# C64Cart.net
KiCad netlist of a schematic drawn in EAGLE
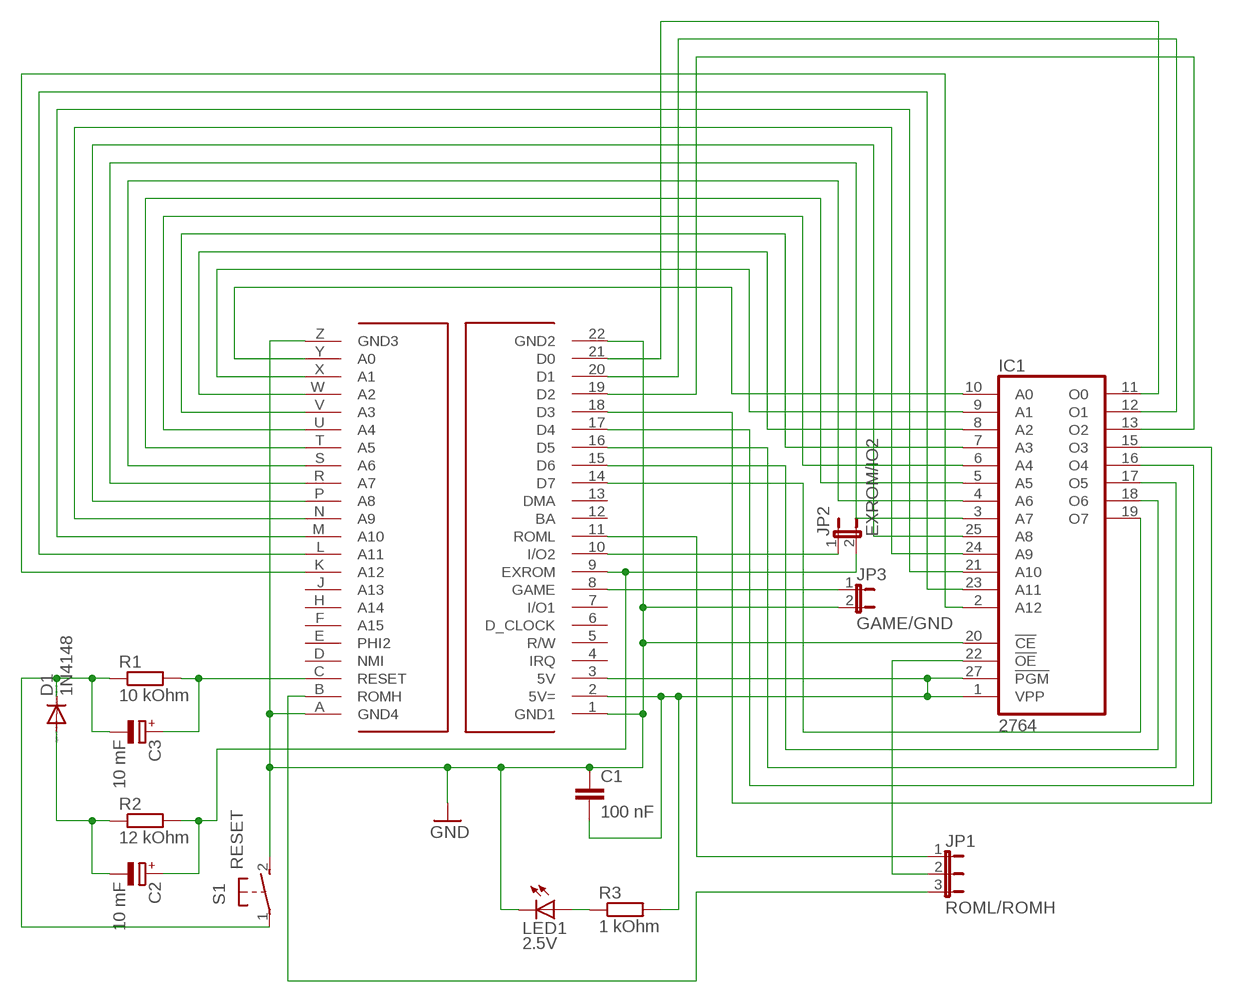
[diagram p0: schematic, sheet 1]

(export (version "E")
  (design (tool "Eeschema 10.0.6"))
  (components
    (comp (ref "C1")
      (value "100 nF")
      (footprint "eagle-import:C050-025X075")
      (libsource (lib "eagle-import") (part "C-EU050-025X075"))
    )
    (comp (ref "C2")
      (value "10 mF")
      (footprint "eagle-import:E2-5")
      (libsource (lib "eagle-import") (part "CPOL-EUE2-5"))
    )
    (comp (ref "C3")
      (value "10 mF")
      (footprint "eagle-import:E2-5")
      (libsource (lib "eagle-import") (part "CPOL-EUE2-5"))
    )
    (comp (ref "D1")
      (value "1N4148")
      (footprint "eagle-import:DO35-7")
      (libsource (lib "eagle-import") (part "1N4148DO35-7"))
    )
    (comp (ref "IC1")
      (value "2764")
      (footprint "eagle-import:DIL28")
      (libsource (lib "eagle-import") (part "2764"))
    )
    (comp (ref "JP1")
      (value "ROML/ROMH")
      (footprint "eagle-import:JP2")
      (libsource (lib "eagle-import") (part "JP2E"))
    )
    (comp (ref "JP2")
      (value "EXROM/IO2")
      (footprint "eagle-import:JP1")
      (libsource (lib "eagle-import") (part "JP1E"))
    )
    (comp (ref "JP3")
      (value "GAME/GND")
      (footprint "eagle-import:JP1")
      (libsource (lib "eagle-import") (part "JP1E"))
    )
    (comp (ref "LED1")
      (value "2.5V")
      (footprint "eagle-import:LED3MM")
      (libsource (lib "eagle-import") (part "LED3MM"))
    )
    (comp (ref "R1")
      (value "10 kOhm")
      (footprint "eagle-import:0204_7")
      (libsource (lib "eagle-import") (part "R-EU_0204/7"))
    )
    (comp (ref "R2")
      (value "12 kOhm")
      (footprint "eagle-import:0204_7")
      (libsource (lib "eagle-import") (part "R-EU_0204/7"))
    )
    (comp (ref "R3")
      (value "1 kOhm")
      (footprint "eagle-import:0204_7")
      (libsource (lib "eagle-import") (part "R-EU_0204/7"))
    )
    (comp (ref "S1")
      (value "RESET")
      (footprint "eagle-import:B3F-31XX")
      (fields (field (name "MPN") "B3F-3100"))
      (libsource (lib "eagle-import") (part "31-XX"))
    )
    (comp (ref "U$1")
      (value "C64_CN")
      (footprint "eagle-import:CARTRIDGE")
      (libsource (lib "eagle-import") (part "CARTRIDGE"))
    )
  )
  (nets
    (net (code "1") (name "GND") (class "Default")
      (node (ref "C1") (pin "1") (pinfunction "1_1") (pintype "passive"))
      (node (ref "IC1") (pin "20") (pinfunction "~{CE}_20") (pintype "input"))
      (node (ref "JP3") (pin "2") (pinfunction "2_2") (pintype "passive"))
      (node (ref "LED1") (pin "K") (pinfunction "C_K") (pintype "passive"))
      (node (ref "S1") (pin "2") (pinfunction "S_2") (pintype "passive"))
      (node (ref "U$1") (pin "1") (pinfunction "GND1_1") (pintype "bidirectional"))
      (node (ref "U$1") (pin "22") (pinfunction "GND2_22") (pintype "bidirectional"))
      (node (ref "U$1") (pin "A") (pinfunction "GND4_A") (pintype "bidirectional"))
      (node (ref "U$1") (pin "Z") (pinfunction "GND3_Z") (pintype "bidirectional"))
    )
    (net (code "2") (name "Net-(C2-Pad-)") (class "Default")
      (node (ref "C2") (pin "-") (pinfunction "-_-") (pintype "passive"))
      (node (ref "D1") (pin "A") (pinfunction "A_A") (pintype "passive"))
      (node (ref "R2") (pin "1") (pinfunction "1_1") (pintype "passive"))
    )
    (net (code "3") (name "Net-(IC1A-A0)") (class "Default")
      (node (ref "IC1") (pin "10") (pinfunction "A0_10") (pintype "input"))
      (node (ref "U$1") (pin "Y") (pinfunction "A0_Y") (pintype "bidirectional"))
    )
    (net (code "4") (name "Net-(IC1A-A1)") (class "Default")
      (node (ref "IC1") (pin "9") (pinfunction "A1_9") (pintype "input"))
      (node (ref "U$1") (pin "X") (pinfunction "A1_X") (pintype "bidirectional"))
    )
    (net (code "5") (name "Net-(IC1A-A2)") (class "Default")
      (node (ref "IC1") (pin "8") (pinfunction "A2_8") (pintype "input"))
      (node (ref "U$1") (pin "W") (pinfunction "A2_W") (pintype "bidirectional"))
    )
    (net (code "6") (name "Net-(IC1A-A3)") (class "Default")
      (node (ref "IC1") (pin "7") (pinfunction "A3_7") (pintype "input"))
      (node (ref "U$1") (pin "V") (pinfunction "A3_V") (pintype "bidirectional"))
    )
    (net (code "7") (name "Net-(IC1A-A4)") (class "Default")
      (node (ref "IC1") (pin "6") (pinfunction "A4_6") (pintype "input"))
      (node (ref "U$1") (pin "U") (pinfunction "A4_U") (pintype "bidirectional"))
    )
    (net (code "8") (name "Net-(IC1A-A5)") (class "Default")
      (node (ref "IC1") (pin "5") (pinfunction "A5_5") (pintype "input"))
      (node (ref "U$1") (pin "T") (pinfunction "A5_T") (pintype "bidirectional"))
    )
    (net (code "9") (name "Net-(IC1A-A6)") (class "Default")
      (node (ref "IC1") (pin "4") (pinfunction "A6_4") (pintype "input"))
      (node (ref "U$1") (pin "S") (pinfunction "A6_S") (pintype "bidirectional"))
    )
    (net (code "10") (name "Net-(IC1A-A7)") (class "Default")
      (node (ref "IC1") (pin "3") (pinfunction "A7_3") (pintype "input"))
      (node (ref "U$1") (pin "R") (pinfunction "A7_R") (pintype "bidirectional"))
    )
    (net (code "11") (name "Net-(IC1A-A8)") (class "Default")
      (node (ref "IC1") (pin "25") (pinfunction "A8_25") (pintype "input"))
      (node (ref "U$1") (pin "P") (pinfunction "A8_P") (pintype "bidirectional"))
    )
    (net (code "12") (name "Net-(IC1A-A9)") (class "Default")
      (node (ref "IC1") (pin "24") (pinfunction "A9_24") (pintype "input"))
      (node (ref "U$1") (pin "N") (pinfunction "A9_N") (pintype "bidirectional"))
    )
    (net (code "13") (name "Net-(IC1A-A10)") (class "Default")
      (node (ref "IC1") (pin "21") (pinfunction "A10_21") (pintype "input"))
      (node (ref "U$1") (pin "M") (pinfunction "A10_M") (pintype "bidirectional"))
    )
    (net (code "14") (name "Net-(IC1A-A11)") (class "Default")
      (node (ref "IC1") (pin "23") (pinfunction "A11_23") (pintype "input"))
      (node (ref "U$1") (pin "L") (pinfunction "A11_L") (pintype "bidirectional"))
    )
    (net (code "15") (name "Net-(IC1A-A12)") (class "Default")
      (node (ref "IC1") (pin "2") (pinfunction "A12_2") (pintype "input"))
      (node (ref "U$1") (pin "K") (pinfunction "A12_K") (pintype "bidirectional"))
    )
    (net (code "16") (name "Net-(IC1A-O0)") (class "Default")
      (node (ref "IC1") (pin "11") (pinfunction "O0_11") (pintype "tri_state"))
      (node (ref "U$1") (pin "21") (pinfunction "D0_21") (pintype "bidirectional"))
    )
    (net (code "17") (name "Net-(IC1A-O1)") (class "Default")
      (node (ref "IC1") (pin "12") (pinfunction "O1_12") (pintype "tri_state"))
      (node (ref "U$1") (pin "20") (pinfunction "D1_20") (pintype "bidirectional"))
    )
    (net (code "18") (name "Net-(IC1A-O2)") (class "Default")
      (node (ref "IC1") (pin "13") (pinfunction "O2_13") (pintype "tri_state"))
      (node (ref "U$1") (pin "19") (pinfunction "D2_19") (pintype "bidirectional"))
    )
    (net (code "19") (name "Net-(IC1A-O3)") (class "Default")
      (node (ref "IC1") (pin "15") (pinfunction "O3_15") (pintype "tri_state"))
      (node (ref "U$1") (pin "18") (pinfunction "D3_18") (pintype "bidirectional"))
    )
    (net (code "20") (name "Net-(IC1A-O4)") (class "Default")
      (node (ref "IC1") (pin "16") (pinfunction "O4_16") (pintype "tri_state"))
      (node (ref "U$1") (pin "17") (pinfunction "D4_17") (pintype "bidirectional"))
    )
    (net (code "21") (name "Net-(IC1A-O5)") (class "Default")
      (node (ref "IC1") (pin "17") (pinfunction "O5_17") (pintype "tri_state"))
      (node (ref "U$1") (pin "16") (pinfunction "D5_16") (pintype "bidirectional"))
    )
    (net (code "22") (name "Net-(IC1A-O6)") (class "Default")
      (node (ref "IC1") (pin "18") (pinfunction "O6_18") (pintype "tri_state"))
      (node (ref "U$1") (pin "15") (pinfunction "D6_15") (pintype "bidirectional"))
    )
    (net (code "23") (name "Net-(IC1A-O7)") (class "Default")
      (node (ref "IC1") (pin "19") (pinfunction "O7_19") (pintype "tri_state"))
      (node (ref "U$1") (pin "14") (pinfunction "D7_14") (pintype "bidirectional"))
    )
    (net (code "24") (name "Net-(IC1A-VPP)") (class "Default")
      (node (ref "C1") (pin "2") (pinfunction "2_2") (pintype "passive"))
      (node (ref "IC1") (pin "1") (pinfunction "VPP_1") (pintype "input"))
      (node (ref "IC1") (pin "27") (pinfunction "~{PGM}_27") (pintype "input"))
      (node (ref "R3") (pin "2") (pinfunction "2_2") (pintype "passive"))
      (node (ref "U$1") (pin "2") (pinfunction "5V=_2") (pintype "bidirectional"))
      (node (ref "U$1") (pin "3") (pinfunction "5V_3") (pintype "bidirectional"))
    )
    (net (code "25") (name "Net-(IC1A-~{OE})") (class "Default")
      (node (ref "IC1") (pin "22") (pinfunction "~{OE}_22") (pintype "input"))
      (node (ref "JP1") (pin "2") (pinfunction "2_2") (pintype "passive"))
    )
    (net (code "26") (name "Net-(LED1-PadA)") (class "Default")
      (node (ref "LED1") (pin "A") (pinfunction "A_A") (pintype "passive"))
      (node (ref "R3") (pin "1") (pinfunction "1_1") (pintype "passive"))
    )
    (net (code "27") (name "Net-(S1-P)") (class "Default")
      (node (ref "C3") (pin "-") (pinfunction "-_-") (pintype "passive"))
      (node (ref "D1") (pin "C") (pinfunction "C_C") (pintype "passive"))
      (node (ref "R1") (pin "1") (pinfunction "1_1") (pintype "passive"))
      (node (ref "S1") (pin "1") (pinfunction "P_1") (pintype "passive"))
    )
    (net (code "28") (name "Net-(U$1-EXROM)") (class "Default")
      (node (ref "C2") (pin "+") (pinfunction "+_+") (pintype "passive"))
      (node (ref "JP2") (pin "2") (pinfunction "2_2") (pintype "passive"))
      (node (ref "R2") (pin "2") (pinfunction "2_2") (pintype "passive"))
      (node (ref "U$1") (pin "9") (pinfunction "EXROM_9") (pintype "bidirectional"))
    )
    (net (code "29") (name "Net-(U$1-GAME)") (class "Default")
      (node (ref "JP3") (pin "1") (pinfunction "1_1") (pintype "passive"))
      (node (ref "U$1") (pin "8") (pinfunction "GAME_8") (pintype "bidirectional"))
    )
    (net (code "30") (name "Net-(U$1-I{slash}O2)") (class "Default")
      (node (ref "JP2") (pin "1") (pinfunction "1_1") (pintype "passive"))
      (node (ref "U$1") (pin "10") (pinfunction "I/O2_10") (pintype "bidirectional"))
    )
    (net (code "31") (name "Net-(U$1-RESET)") (class "Default")
      (node (ref "C3") (pin "+") (pinfunction "+_+") (pintype "passive"))
      (node (ref "R1") (pin "2") (pinfunction "2_2") (pintype "passive"))
      (node (ref "U$1") (pin "C") (pinfunction "RESET_C") (pintype "bidirectional"))
    )
    (net (code "32") (name "Net-(U$1-ROMH)") (class "Default")
      (node (ref "JP1") (pin "3") (pinfunction "3_3") (pintype "passive"))
      (node (ref "U$1") (pin "B") (pinfunction "ROMH_B") (pintype "bidirectional"))
    )
    (net (code "33") (name "Net-(U$1-ROML)") (class "Default")
      (node (ref "JP1") (pin "1") (pinfunction "1_1") (pintype "passive"))
      (node (ref "U$1") (pin "11") (pinfunction "ROML_11") (pintype "bidirectional"))
    )
    (net (code "34") (name "unconnected-(U$1-A13-PadJ)") (class "Default")
      (node (ref "U$1") (pin "J") (pinfunction "A13_J") (pintype "bidirectional"))
    )
    (net (code "35") (name "unconnected-(U$1-A14-PadH)") (class "Default")
      (node (ref "U$1") (pin "H") (pinfunction "A14_H") (pintype "bidirectional"))
    )
    (net (code "36") (name "unconnected-(U$1-A15-PadF)") (class "Default")
      (node (ref "U$1") (pin "F") (pinfunction "A15_F") (pintype "bidirectional"))
    )
    (net (code "37") (name "unconnected-(U$1-BA-Pad12)") (class "Default")
      (node (ref "U$1") (pin "12") (pinfunction "BA_12") (pintype "bidirectional"))
    )
    (net (code "38") (name "unconnected-(U$1-DMA-Pad13)") (class "Default")
      (node (ref "U$1") (pin "13") (pinfunction "DMA_13") (pintype "bidirectional"))
    )
    (net (code "39") (name "unconnected-(U$1-D_CLOCK-Pad6)") (class "Default")
      (node (ref "U$1") (pin "6") (pinfunction "D_CLOCK_6") (pintype "bidirectional"))
    )
    (net (code "40") (name "unconnected-(U$1-IRQ-Pad4)") (class "Default")
      (node (ref "U$1") (pin "4") (pinfunction "IRQ_4") (pintype "bidirectional"))
    )
    (net (code "41") (name "unconnected-(U$1-I{slash}O1-Pad7)") (class "Default")
      (node (ref "U$1") (pin "7") (pinfunction "I/O1_7") (pintype "bidirectional"))
    )
    (net (code "42") (name "unconnected-(U$1-NMI-PadD)") (class "Default")
      (node (ref "U$1") (pin "D") (pinfunction "NMI_D") (pintype "bidirectional"))
    )
    (net (code "43") (name "unconnected-(U$1-PHI2-PadE)") (class "Default")
      (node (ref "U$1") (pin "E") (pinfunction "PHI2_E") (pintype "bidirectional"))
    )
    (net (code "44") (name "unconnected-(U$1-R{slash}W-Pad5)") (class "Default")
      (node (ref "U$1") (pin "5") (pinfunction "R/W_5") (pintype "bidirectional"))
    )
  )
)
